# strip_02.net
KiCad netlist of a schematic drawn in EAGLE
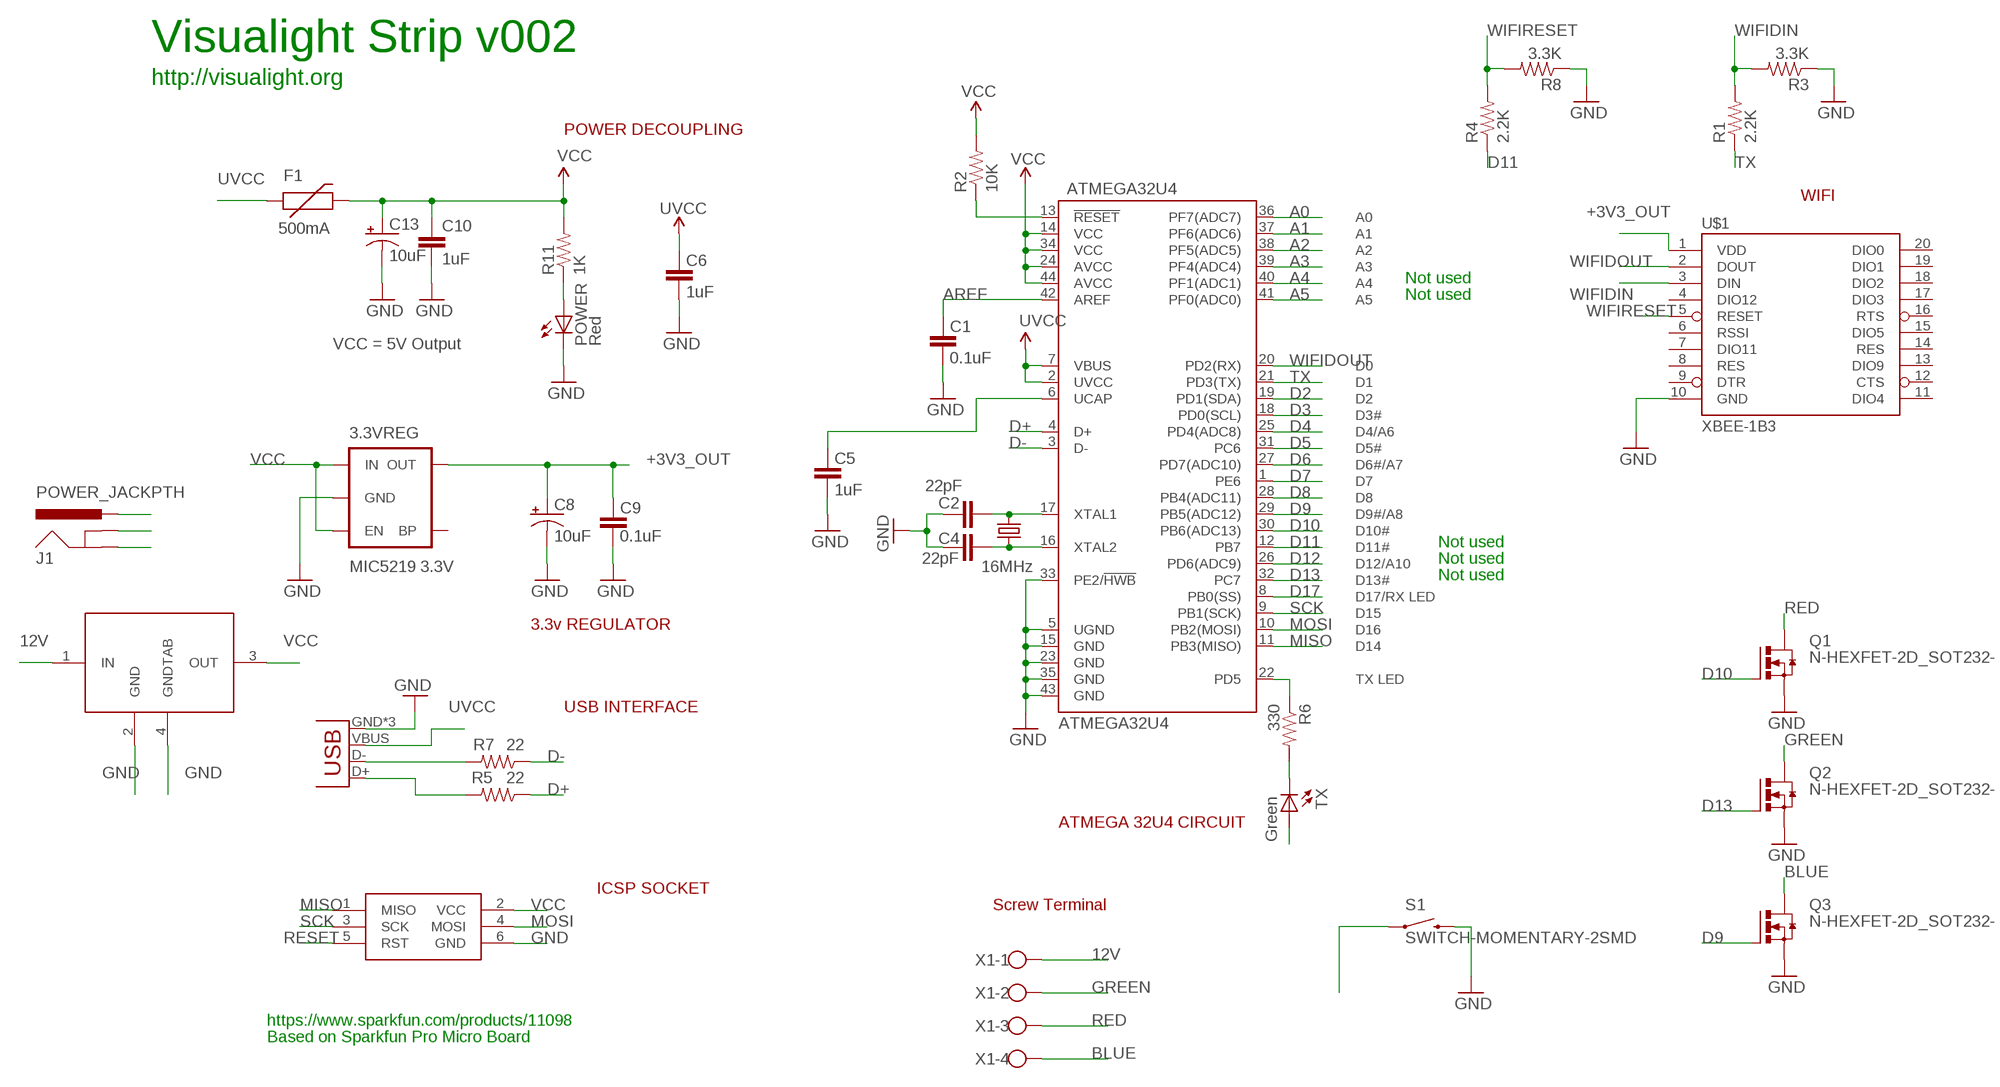
[diagram p0: schematic, sheet 1]

(export (version "E")
  (design (tool "Eeschema 10.0.6"))
  (components
    (comp (ref "3.3VREG")
      (value "MIC5219 3.3V")
      (footprint "eagle-import:SOT23-5")
      (libsource (lib "eagle-import") (part "V_REG_MIC52193.3V"))
    )
    (comp (ref "ATMEGA32U4")
      (value "ATMEGA32U4")
      (footprint "eagle-import:SPARKFUN-DIGITALIC_TQFP44")
      (libsource (lib "eagle-import") (part "ATMEGA32U4TQFP"))
    )
    (comp (ref "C1")
      (value "0.1uF")
      (footprint "eagle-import:0402-CAP")
      (libsource (lib "eagle-import") (part "CAP0402-CAP"))
    )
    (comp (ref "C2")
      (value "22pF")
      (footprint "eagle-import:0402-CAP")
      (libsource (lib "eagle-import") (part "CAP0402-CAP"))
    )
    (comp (ref "C4")
      (value "22pF")
      (footprint "eagle-import:0402-CAP")
      (libsource (lib "eagle-import") (part "CAP0402-CAP"))
    )
    (comp (ref "C5")
      (value "1uF")
      (footprint "eagle-import:0402-CAP")
      (libsource (lib "eagle-import") (part "CAP0402-CAP"))
    )
    (comp (ref "C6")
      (value "1uF")
      (footprint "eagle-import:0402-CAP")
      (libsource (lib "eagle-import") (part "CAP0402-CAP"))
    )
    (comp (ref "C8")
      (value "10uF")
      (footprint "eagle-import:EIA3216")
      (libsource (lib "eagle-import") (part "CAP_POL1206"))
    )
    (comp (ref "C9")
      (value "0.1uF")
      (footprint "eagle-import:0402-CAP")
      (libsource (lib "eagle-import") (part "CAP0402-CAP"))
    )
    (comp (ref "C10")
      (value "1uF")
      (footprint "eagle-import:0402-CAP")
      (libsource (lib "eagle-import") (part "CAP0402-CAP"))
    )
    (comp (ref "C13")
      (value "10uF")
      (footprint "eagle-import:EIA3216")
      (libsource (lib "eagle-import") (part "CAP_POL1206"))
    )
    (comp (ref "F1")
      (value "500mA")
      (footprint "eagle-import:PTC-1206")
      (libsource (lib "eagle-import") (part "PTCSMD"))
    )
    (comp (ref "ISP1")
      (value "AVRISP-6")
      (footprint "eagle-import:AVRISP")
      (libsource (lib "eagle-import") (part "AVRISP-6"))
    )
    (comp (ref "J1")
      (value "POWER_JACKPTH")
      (footprint "eagle-import:POWER_JACK_PTH")
      (libsource (lib "eagle-import") (part "POWER_JACKPTH"))
    )
    (comp (ref "POWER")
      (value "Red")
      (footprint "eagle-import:LED-0603")
      (libsource (lib "eagle-import") (part "LED0603"))
    )
    (comp (ref "Q1")
      (value "N-HEXFET-2D_SOT232-")
      (footprint "eagle-import:SOT223")
      (libsource (lib "eagle-import") (part "N-HEXFET-2D_?-SOT232"))
    )
    (comp (ref "Q2")
      (value "N-HEXFET-2D_SOT232-")
      (footprint "eagle-import:SOT223")
      (libsource (lib "eagle-import") (part "N-HEXFET-2D_?-SOT232"))
    )
    (comp (ref "Q3")
      (value "N-HEXFET-2D_SOT232-")
      (footprint "eagle-import:SOT223")
      (libsource (lib "eagle-import") (part "N-HEXFET-2D_?-SOT232"))
    )
    (comp (ref "R1")
      (value "2.2K")
      (footprint "eagle-import:0402-RES")
      (libsource (lib "eagle-import") (part "RESISTOR0402-RES"))
    )
    (comp (ref "R2")
      (value "10K")
      (footprint "eagle-import:0402-RES")
      (libsource (lib "eagle-import") (part "RESISTOR0402-RES"))
    )
    (comp (ref "R3")
      (value "3.3K")
      (footprint "eagle-import:0402-RES")
      (libsource (lib "eagle-import") (part "RESISTOR0402-RES"))
    )
    (comp (ref "R4")
      (value "2.2K")
      (footprint "eagle-import:0402-RES")
      (libsource (lib "eagle-import") (part "RESISTOR0402-RES"))
    )
    (comp (ref "R5")
      (value "22")
      (footprint "eagle-import:0402-RES")
      (libsource (lib "eagle-import") (part "RESISTOR0402-RES"))
    )
    (comp (ref "R6")
      (value "330")
      (footprint "eagle-import:0402-RES")
      (libsource (lib "eagle-import") (part "RESISTOR0402-RES"))
    )
    (comp (ref "R7")
      (value "22")
      (footprint "eagle-import:0402-RES")
      (libsource (lib "eagle-import") (part "RESISTOR0402-RES"))
    )
    (comp (ref "R8")
      (value "3.3K")
      (footprint "eagle-import:0402-RES")
      (libsource (lib "eagle-import") (part "RESISTOR0402-RES"))
    )
    (comp (ref "R11")
      (value "1K")
      (footprint "eagle-import:0402-RES")
      (libsource (lib "eagle-import") (part "RESISTOR0402-RES"))
    )
    (comp (ref "S1")
      (value "SWITCH-MOMENTARY-2SMD")
      (footprint "eagle-import:TACTILE_SWITCH_SMD")
      (libsource (lib "eagle-import") (part "SWITCH-MOMENTARY-2SMD"))
    )
    (comp (ref "TX")
      (value "Green")
      (footprint "eagle-import:LED-0603")
      (libsource (lib "eagle-import") (part "LED0603"))
    )
    (comp (ref "U$1")
      (value "XBEE-1B3")
      (footprint "eagle-import:XBEE-SMD")
      (libsource (lib "eagle-import") (part "XBEE-1B3"))
    )
    (comp (ref "U$2")
      (value "MIC5239")
      (footprint "eagle-import:SOT223")
      (libsource (lib "eagle-import") (part "MIC5239"))
    )
    (comp (ref "X1")
      (value "W237-4")
      (footprint "eagle-import:W237-4")
      (libsource (lib "eagle-import") (part "W237-4"))
    )
    (comp (ref "X2")
      (value "USB-MICROB")
      (footprint "eagle-import:USB-MICROB")
      (libsource (lib "eagle-import") (part "USB-MICROB"))
    )
    (comp (ref "Y1")
      (value "16MHz")
      (footprint "eagle-import:CRYSTAL-SMD-5X3")
      (libsource (lib "eagle-import") (part "CRYSTAL5X3"))
    )
  )
  (nets
    (net (code "1") (name "/+3V3_OUT") (class "Default")
      (node (ref "3.3VREG") (pin "5") (pinfunction "OUT_5") (pintype "passive"))
      (node (ref "C8") (pin "A") (pinfunction "+_A") (pintype "passive"))
      (node (ref "C9") (pin "2") (pinfunction "2_2") (pintype "passive"))
      (node (ref "U$1") (pin "1") (pinfunction "VDD_1") (pintype "power_in"))
    )
    (net (code "2") (name "/12V") (class "Default")
      (node (ref "J1") (pin "PWR") (pinfunction "PWR_PWR") (pintype "bidirectional"))
      (node (ref "U$2") (pin "1") (pinfunction "IN_1") (pintype "input"))
      (node (ref "X1") (pin "1") (pinfunction "KL_1") (pintype "passive"))
    )
    (net (code "3") (name "/A0") (class "Default")
      (node (ref "ATMEGA32U4") (pin "36") (pinfunction "PF7(ADC7)_36") (pintype "bidirectional"))
    )
    (net (code "4") (name "/A1") (class "Default")
      (node (ref "ATMEGA32U4") (pin "37") (pinfunction "PF6(ADC6)_37") (pintype "bidirectional"))
    )
    (net (code "5") (name "/A2") (class "Default")
      (node (ref "ATMEGA32U4") (pin "38") (pinfunction "PF5(ADC5)_38") (pintype "bidirectional"))
    )
    (net (code "6") (name "/A3") (class "Default")
      (node (ref "ATMEGA32U4") (pin "39") (pinfunction "PF4(ADC4)_39") (pintype "bidirectional"))
    )
    (net (code "7") (name "/A4") (class "Default")
      (node (ref "ATMEGA32U4") (pin "40") (pinfunction "PF1(ADC1)_40") (pintype "bidirectional"))
    )
    (net (code "8") (name "/A5") (class "Default")
      (node (ref "ATMEGA32U4") (pin "41") (pinfunction "PF0(ADC0)_41") (pintype "bidirectional"))
    )
    (net (code "9") (name "/AREF") (class "Default")
      (node (ref "ATMEGA32U4") (pin "42") (pinfunction "AREF_42") (pintype "bidirectional"))
      (node (ref "C1") (pin "2") (pinfunction "2_2") (pintype "passive"))
    )
    (net (code "10") (name "/BLUE") (class "Default")
      (node (ref "Q3") (pin "2") (pinfunction "D_2") (pintype "passive"))
      (node (ref "Q3") (pin "4") (pinfunction "D_4") (pintype "passive"))
      (node (ref "X1") (pin "4") (pinfunction "KL_4") (pintype "passive"))
    )
    (net (code "11") (name "/D+") (class "Default")
      (node (ref "ATMEGA32U4") (pin "4") (pinfunction "D+_4") (pintype "bidirectional"))
      (node (ref "R5") (pin "1") (pinfunction "1_1") (pintype "passive"))
    )
    (net (code "12") (name "/D-") (class "Default")
      (node (ref "ATMEGA32U4") (pin "3") (pinfunction "D-_3") (pintype "bidirectional"))
      (node (ref "R7") (pin "1") (pinfunction "1_1") (pintype "passive"))
    )
    (net (code "13") (name "/D2") (class "Default")
      (node (ref "ATMEGA32U4") (pin "19") (pinfunction "PD1(SDA)_19") (pintype "bidirectional"))
    )
    (net (code "14") (name "/D3") (class "Default")
      (node (ref "ATMEGA32U4") (pin "18") (pinfunction "PD0(SCL)_18") (pintype "bidirectional"))
    )
    (net (code "15") (name "/D4") (class "Default")
      (node (ref "ATMEGA32U4") (pin "25") (pinfunction "PD4(ADC8)_25") (pintype "bidirectional"))
    )
    (net (code "16") (name "/D5") (class "Default")
      (node (ref "ATMEGA32U4") (pin "31") (pinfunction "PC6_31") (pintype "bidirectional"))
    )
    (net (code "17") (name "/D6") (class "Default")
      (node (ref "ATMEGA32U4") (pin "27") (pinfunction "PD7(ADC10)_27") (pintype "bidirectional"))
    )
    (net (code "18") (name "/D7") (class "Default")
      (node (ref "ATMEGA32U4") (pin "1") (pinfunction "PE6_1") (pintype "bidirectional"))
      (node (ref "S1") (pin "1") (pinfunction "1_1") (pintype "passive"))
    )
    (net (code "19") (name "/D8") (class "Default")
      (node (ref "ATMEGA32U4") (pin "28") (pinfunction "PB4(ADC11)_28") (pintype "bidirectional"))
    )
    (net (code "20") (name "/D9") (class "Default")
      (node (ref "ATMEGA32U4") (pin "29") (pinfunction "PB5(ADC12)_29") (pintype "bidirectional"))
      (node (ref "Q3") (pin "1") (pinfunction "G_1") (pintype "passive"))
    )
    (net (code "21") (name "/D10") (class "Default")
      (node (ref "ATMEGA32U4") (pin "30") (pinfunction "PB6(ADC13)_30") (pintype "bidirectional"))
      (node (ref "Q1") (pin "1") (pinfunction "G_1") (pintype "passive"))
    )
    (net (code "22") (name "/D11") (class "Default")
      (node (ref "ATMEGA32U4") (pin "12") (pinfunction "PB7_12") (pintype "bidirectional"))
      (node (ref "R4") (pin "1") (pinfunction "1_1") (pintype "passive"))
    )
    (net (code "23") (name "/D12") (class "Default")
      (node (ref "ATMEGA32U4") (pin "26") (pinfunction "PD6(ADC9)_26") (pintype "bidirectional"))
    )
    (net (code "24") (name "/D13") (class "Default")
      (node (ref "ATMEGA32U4") (pin "32") (pinfunction "PC7_32") (pintype "bidirectional"))
      (node (ref "Q2") (pin "1") (pinfunction "G_1") (pintype "passive"))
    )
    (net (code "25") (name "/D17") (class "Default")
      (node (ref "ATMEGA32U4") (pin "8") (pinfunction "PB0(SS)_8") (pintype "bidirectional"))
    )
    (net (code "26") (name "/GREEN") (class "Default")
      (node (ref "Q2") (pin "2") (pinfunction "D_2") (pintype "passive"))
      (node (ref "Q2") (pin "4") (pinfunction "D_4") (pintype "passive"))
      (node (ref "X1") (pin "2") (pinfunction "KL_2") (pintype "passive"))
    )
    (net (code "27") (name "/MISO") (class "Default")
      (node (ref "ATMEGA32U4") (pin "11") (pinfunction "PB3(MISO)_11") (pintype "bidirectional"))
      (node (ref "ISP1") (pin "1") (pinfunction "MISO_1") (pintype "input"))
    )
    (net (code "28") (name "/MOSI") (class "Default")
      (node (ref "ATMEGA32U4") (pin "10") (pinfunction "PB2(MOSI)_10") (pintype "bidirectional"))
      (node (ref "ISP1") (pin "4") (pinfunction "MOSI_4") (pintype "output"))
    )
    (net (code "29") (name "/RED") (class "Default")
      (node (ref "Q1") (pin "2") (pinfunction "D_2") (pintype "passive"))
      (node (ref "Q1") (pin "4") (pinfunction "D_4") (pintype "passive"))
      (node (ref "X1") (pin "3") (pinfunction "KL_3") (pintype "passive"))
    )
    (net (code "30") (name "/RESET") (class "Default")
      (node (ref "ATMEGA32U4") (pin "13") (pinfunction "~{RESET}_13") (pintype "bidirectional"))
      (node (ref "ISP1") (pin "5") (pinfunction "RST_5") (pintype "output"))
      (node (ref "R2") (pin "1") (pinfunction "1_1") (pintype "passive"))
    )
    (net (code "31") (name "/SCK") (class "Default")
      (node (ref "ATMEGA32U4") (pin "9") (pinfunction "PB1(SCK)_9") (pintype "bidirectional"))
      (node (ref "ISP1") (pin "3") (pinfunction "SCK_3") (pintype "output"))
    )
    (net (code "32") (name "/TX") (class "Default")
      (node (ref "ATMEGA32U4") (pin "21") (pinfunction "PD3(TX)_21") (pintype "bidirectional"))
      (node (ref "R1") (pin "1") (pinfunction "1_1") (pintype "passive"))
    )
    (net (code "33") (name "/WIFIDIN") (class "Default")
      (node (ref "R1") (pin "2") (pinfunction "2_2") (pintype "passive"))
      (node (ref "R3") (pin "2") (pinfunction "2_2") (pintype "passive"))
      (node (ref "U$1") (pin "3") (pinfunction "DIN_3") (pintype "input"))
    )
    (net (code "34") (name "/WIFIDOUT") (class "Default")
      (node (ref "ATMEGA32U4") (pin "20") (pinfunction "PD2(RX)_20") (pintype "bidirectional"))
      (node (ref "U$1") (pin "2") (pinfunction "DOUT_2") (pintype "output"))
    )
    (net (code "35") (name "/WIFIRESET") (class "Default")
      (node (ref "R4") (pin "2") (pinfunction "2_2") (pintype "passive"))
      (node (ref "R8") (pin "2") (pinfunction "2_2") (pintype "passive"))
      (node (ref "U$1") (pin "5") (pinfunction "RESET_5") (pintype "input"))
    )
    (net (code "36") (name "GND") (class "Default")
      (node (ref "3.3VREG") (pin "2") (pinfunction "GND_2") (pintype "input"))
      (node (ref "ATMEGA32U4") (pin "15") (pinfunction "GND_15") (pintype "bidirectional"))
      (node (ref "ATMEGA32U4") (pin "23") (pinfunction "GND_23") (pintype "bidirectional"))
      (node (ref "ATMEGA32U4") (pin "33") (pinfunction "PE2/~{HWB}_33") (pintype "bidirectional"))
      (node (ref "ATMEGA32U4") (pin "35") (pinfunction "GND_35") (pintype "bidirectional"))
      (node (ref "ATMEGA32U4") (pin "43") (pinfunction "GND_43") (pintype "bidirectional"))
      (node (ref "ATMEGA32U4") (pin "5") (pinfunction "UGND_5") (pintype "bidirectional"))
      (node (ref "C1") (pin "1") (pinfunction "1_1") (pintype "passive"))
      (node (ref "C10") (pin "2") (pinfunction "2_2") (pintype "passive"))
      (node (ref "C13") (pin "C") (pinfunction "-_C") (pintype "passive"))
      (node (ref "C2") (pin "2") (pinfunction "2_2") (pintype "passive"))
      (node (ref "C4") (pin "2") (pinfunction "2_2") (pintype "passive"))
      (node (ref "C5") (pin "1") (pinfunction "1_1") (pintype "passive"))
      (node (ref "C6") (pin "1") (pinfunction "1_1") (pintype "passive"))
      (node (ref "C8") (pin "C") (pinfunction "-_C") (pintype "passive"))
      (node (ref "C9") (pin "1") (pinfunction "1_1") (pintype "passive"))
      (node (ref "ISP1") (pin "6") (pinfunction "GND_6") (pintype "power_in"))
      (node (ref "J1") (pin "GND") (pinfunction "GND_GND") (pintype "bidirectional"))
      (node (ref "J1") (pin "GNDBREAK") (pinfunction "GNDBREAK_GNDBREAK") (pintype "bidirectional"))
      (node (ref "POWER") (pin "C") (pinfunction "C_C") (pintype "passive"))
      (node (ref "Q1") (pin "3") (pinfunction "S_3") (pintype "passive"))
      (node (ref "Q2") (pin "3") (pinfunction "S_3") (pintype "passive"))
      (node (ref "Q3") (pin "3") (pinfunction "S_3") (pintype "passive"))
      (node (ref "R3") (pin "1") (pinfunction "1_1") (pintype "passive"))
      (node (ref "R8") (pin "1") (pinfunction "1_1") (pintype "passive"))
      (node (ref "S1") (pin "3") (pinfunction "2_3") (pintype "passive"))
      (node (ref "U$1") (pin "10") (pinfunction "GND_10") (pintype "power_in"))
      (node (ref "U$2") (pin "2") (pinfunction "GND_2") (pintype "power_in"))
      (node (ref "U$2") (pin "4") (pinfunction "GNDTAB_4") (pintype "power_in"))
      (node (ref "X2") (pin "GND") (pinfunction "GND_GND") (pintype "bidirectional"))
      (node (ref "X2") (pin "MT1") (pinfunction "GND_MT1") (pintype "bidirectional"))
      (node (ref "X2") (pin "MT2") (pinfunction "GND_MT2") (pintype "bidirectional"))
    )
    (net (code "37") (name "Net-(ATMEGA32U4-PD5)") (class "Default")
      (node (ref "ATMEGA32U4") (pin "22") (pinfunction "PD5_22") (pintype "bidirectional"))
      (node (ref "R6") (pin "1") (pinfunction "1_1") (pintype "passive"))
    )
    (net (code "38") (name "Net-(ATMEGA32U4-UCAP)") (class "Default")
      (node (ref "ATMEGA32U4") (pin "6") (pinfunction "UCAP_6") (pintype "bidirectional"))
      (node (ref "C5") (pin "2") (pinfunction "2_2") (pintype "passive"))
    )
    (net (code "39") (name "Net-(ATMEGA32U4-XTAL1)") (class "Default")
      (node (ref "ATMEGA32U4") (pin "17") (pinfunction "XTAL1_17") (pintype "bidirectional"))
      (node (ref "C2") (pin "1") (pinfunction "1_1") (pintype "passive"))
      (node (ref "Y1") (pin "3") (pinfunction "2_3") (pintype "passive"))
    )
    (net (code "40") (name "Net-(ATMEGA32U4-XTAL2)") (class "Default")
      (node (ref "ATMEGA32U4") (pin "16") (pinfunction "XTAL2_16") (pintype "bidirectional"))
      (node (ref "C4") (pin "1") (pinfunction "1_1") (pintype "passive"))
      (node (ref "Y1") (pin "1") (pinfunction "1_1") (pintype "passive"))
    )
    (net (code "41") (name "Net-(POWER-PadA)") (class "Default")
      (node (ref "POWER") (pin "A") (pinfunction "A_A") (pintype "passive"))
      (node (ref "R11") (pin "1") (pinfunction "1_1") (pintype "passive"))
    )
    (net (code "42") (name "Net-(R5-Pad2)") (class "Default")
      (node (ref "R5") (pin "2") (pinfunction "2_2") (pintype "passive"))
      (node (ref "X2") (pin "D+") (pinfunction "D+_D+") (pintype "bidirectional"))
    )
    (net (code "43") (name "Net-(R6-Pad2)") (class "Default")
      (node (ref "R6") (pin "2") (pinfunction "2_2") (pintype "passive"))
      (node (ref "TX") (pin "C") (pinfunction "C_C") (pintype "passive"))
    )
    (net (code "44") (name "Net-(R7-Pad2)") (class "Default")
      (node (ref "R7") (pin "2") (pinfunction "2_2") (pintype "passive"))
      (node (ref "X2") (pin "D-") (pinfunction "D-_D-") (pintype "bidirectional"))
    )
    (net (code "45") (name "UVCC") (class "Default")
      (node (ref "ATMEGA32U4") (pin "2") (pinfunction "UVCC_2") (pintype "bidirectional"))
      (node (ref "ATMEGA32U4") (pin "7") (pinfunction "VBUS_7") (pintype "bidirectional"))
      (node (ref "C6") (pin "2") (pinfunction "2_2") (pintype "passive"))
      (node (ref "F1") (pin "1") (pinfunction "1_1") (pintype "bidirectional"))
      (node (ref "X2") (pin "VBUS") (pinfunction "VBUS_VBUS") (pintype "bidirectional"))
    )
    (net (code "46") (name "VCC") (class "Default")
      (node (ref "3.3VREG") (pin "1") (pinfunction "IN_1") (pintype "input"))
      (node (ref "3.3VREG") (pin "3") (pinfunction "EN_3") (pintype "input"))
      (node (ref "ATMEGA32U4") (pin "14") (pinfunction "VCC_14") (pintype "bidirectional"))
      (node (ref "ATMEGA32U4") (pin "24") (pinfunction "AVCC_24") (pintype "bidirectional"))
      (node (ref "ATMEGA32U4") (pin "34") (pinfunction "VCC_34") (pintype "bidirectional"))
      (node (ref "ATMEGA32U4") (pin "44") (pinfunction "AVCC_44") (pintype "bidirectional"))
      (node (ref "C10") (pin "1") (pinfunction "1_1") (pintype "passive"))
      (node (ref "C13") (pin "A") (pinfunction "+_A") (pintype "passive"))
      (node (ref "F1") (pin "2") (pinfunction "2_2") (pintype "bidirectional"))
      (node (ref "ISP1") (pin "2") (pinfunction "VCC_2") (pintype "power_in"))
      (node (ref "R11") (pin "2") (pinfunction "2_2") (pintype "passive"))
      (node (ref "R2") (pin "2") (pinfunction "2_2") (pintype "passive"))
      (node (ref "TX") (pin "A") (pinfunction "A_A") (pintype "passive"))
      (node (ref "U$2") (pin "3") (pinfunction "OUT_3") (pintype "output"))
    )
    (net (code "47") (name "unconnected-(3.3VREG-BP-Pad4)") (class "Default")
      (node (ref "3.3VREG") (pin "4") (pinfunction "BP_4") (pintype "input"))
    )
    (net (code "48") (name "unconnected-(U$1-CTS-Pad12)") (class "Default")
      (node (ref "U$1") (pin "12") (pinfunction "CTS_12") (pintype "output"))
    )
    (net (code "49") (name "unconnected-(U$1-DIO0-Pad20)") (class "Default")
      (node (ref "U$1") (pin "20") (pinfunction "DIO0_20") (pintype "bidirectional"))
    )
    (net (code "50") (name "unconnected-(U$1-DIO1-Pad19)") (class "Default")
      (node (ref "U$1") (pin "19") (pinfunction "DIO1_19") (pintype "bidirectional"))
    )
    (net (code "51") (name "unconnected-(U$1-DIO2-Pad18)") (class "Default")
      (node (ref "U$1") (pin "18") (pinfunction "DIO2_18") (pintype "bidirectional"))
    )
    (net (code "52") (name "unconnected-(U$1-DIO3-Pad17)") (class "Default")
      (node (ref "U$1") (pin "17") (pinfunction "DIO3_17") (pintype "bidirectional"))
    )
    (net (code "53") (name "unconnected-(U$1-DIO4-Pad11)") (class "Default")
      (node (ref "U$1") (pin "11") (pinfunction "DIO4_11") (pintype "bidirectional"))
    )
    (net (code "54") (name "unconnected-(U$1-DIO5-Pad15)") (class "Default")
      (node (ref "U$1") (pin "15") (pinfunction "DIO5_15") (pintype "bidirectional"))
    )
    (net (code "55") (name "unconnected-(U$1-DIO9-Pad13)") (class "Default")
      (node (ref "U$1") (pin "13") (pinfunction "DIO9_13") (pintype "bidirectional"))
    )
    (net (code "56") (name "unconnected-(U$1-DIO11-Pad7)") (class "Default")
      (node (ref "U$1") (pin "7") (pinfunction "DIO11_7") (pintype "bidirectional"))
    )
    (net (code "57") (name "unconnected-(U$1-DIO12-Pad4)") (class "Default")
      (node (ref "U$1") (pin "4") (pinfunction "DIO12_4") (pintype "bidirectional"))
    )
    (net (code "58") (name "unconnected-(U$1-DTR-Pad9)") (class "Default")
      (node (ref "U$1") (pin "9") (pinfunction "DTR_9") (pintype "bidirectional"))
    )
    (net (code "59") (name "unconnected-(U$1-RES-Pad8)") (class "Default")
      (node (ref "U$1") (pin "8") (pinfunction "RES_8") (pintype "bidirectional"))
    )
    (net (code "60") (name "unconnected-(U$1-RES-Pad14)") (class "Default")
      (node (ref "U$1") (pin "14") (pinfunction "RES_14") (pintype "bidirectional"))
    )
    (net (code "61") (name "unconnected-(U$1-RSSI-Pad6)") (class "Default")
      (node (ref "U$1") (pin "6") (pinfunction "RSSI_6") (pintype "bidirectional"))
    )
    (net (code "62") (name "unconnected-(U$1-RTS-Pad16)") (class "Default")
      (node (ref "U$1") (pin "16") (pinfunction "RTS_16") (pintype "input"))
    )
  )
)
